# SCH_ninth-easy-stackable_2023-01-05.net
KiCad netlist of a schematic drawn in EasyEDA
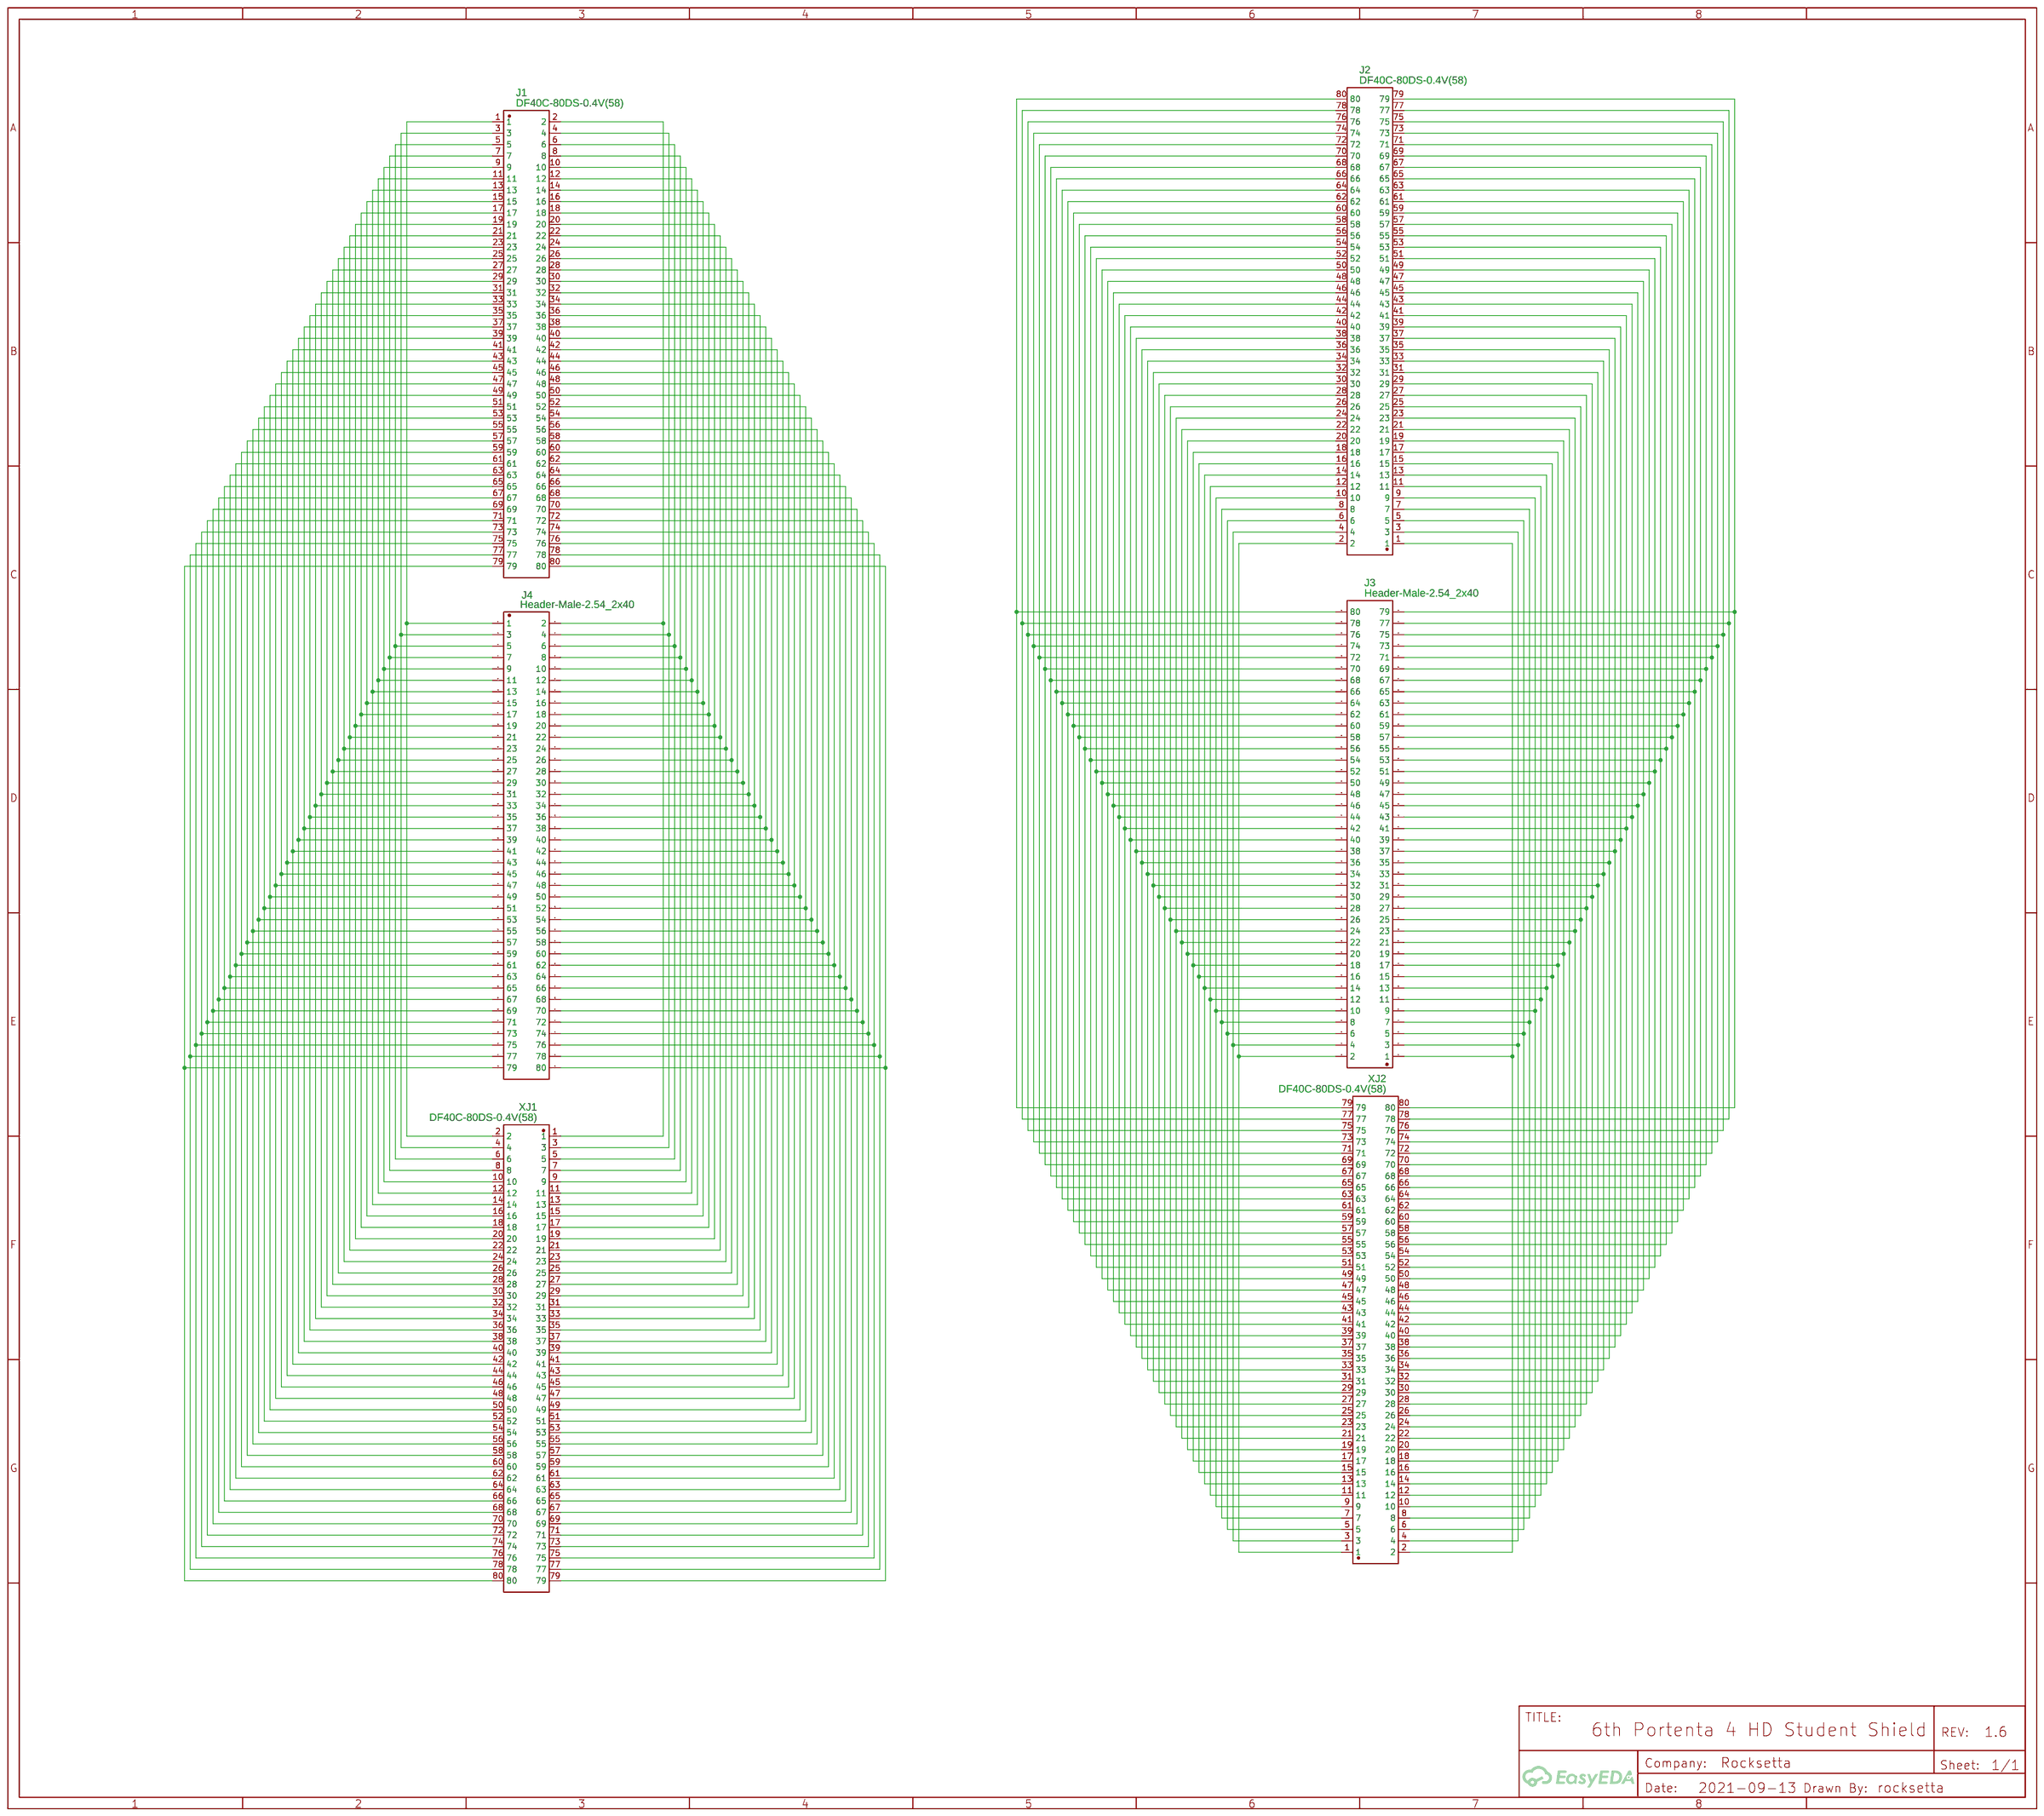
[diagram p0: schematic sheet]

(export (version "E")
  (design (tool "Eeschema 10.0.6"))
  (components
    (comp (ref "J1")
      (value "DF40C-80DS-0.4V(58)")
      (fields (field (name "BOM_Supplier Part") "C597941"))
      (libsource (lib "") (part "DF40C-80DS-0.4V(58)_2"))
    )
    (comp (ref "J2")
      (value "DF40C-80DS-0.4V(58)")
      (fields (field (name "BOM_Supplier Part") "C597941"))
      (libsource (lib "") (part "DF40C-80DS-0.4V(58)_3"))
    )
    (comp (ref "J3")
      (value "Header-Male-2.54_2x40")
      (fields
        (field (name "BOM_Manufacturer Part") "2.54mm 2x40P")
        (field (name "BOM_Supplier Part") "C2333")
      )
      (libsource (lib "") (part "Header-Male-2.54_2x40_1"))
    )
    (comp (ref "J4")
      (value "Header-Male-2.54_2x40")
      (fields
        (field (name "BOM_Manufacturer Part") "2.54mm 2x40P")
        (field (name "BOM_Supplier Part") "C2333")
      )
      (libsource (lib "") (part "Header-Male-2.54_2x40"))
    )
    (comp (ref "XJ1")
      (value "DF40C-80DS-0.4V(58)")
      (fields (field (name "BOM_Supplier Part") "C597941"))
      (libsource (lib "") (part "DF40C-80DS-0.4V(58)"))
    )
    (comp (ref "XJ2")
      (value "DF40C-80DS-0.4V(58)")
      (fields (field (name "BOM_Supplier Part") "C597941"))
      (libsource (lib "") (part "DF40C-80DS-0.4V(58)_1"))
    )
  )
  (nets
    (net (code "1") (name "Net-(J1-Pad1)") (class "Default")
      (node (ref "J1") (pin "1") (pinfunction "1_1") (pintype "unspecified"))
      (node (ref "J4") (pin "1") (pinfunction "1_1") (pintype "unspecified"))
      (node (ref "XJ1") (pin "2") (pinfunction "2_2") (pintype "unspecified"))
    )
    (net (code "2") (name "Net-(J1-Pad2)") (class "Default")
      (node (ref "J1") (pin "2") (pinfunction "2_2") (pintype "unspecified"))
      (node (ref "J4") (pin "2") (pinfunction "2_2") (pintype "unspecified"))
      (node (ref "XJ1") (pin "1") (pinfunction "1_1") (pintype "unspecified"))
    )
    (net (code "3") (name "Net-(J1-Pad3)") (class "Default")
      (node (ref "J1") (pin "3") (pinfunction "3_3") (pintype "unspecified"))
      (node (ref "J4") (pin "3") (pinfunction "3_3") (pintype "unspecified"))
      (node (ref "XJ1") (pin "4") (pinfunction "4_4") (pintype "unspecified"))
    )
    (net (code "4") (name "Net-(J1-Pad4)") (class "Default")
      (node (ref "J1") (pin "4") (pinfunction "4_4") (pintype "unspecified"))
      (node (ref "J4") (pin "4") (pinfunction "4_4") (pintype "unspecified"))
      (node (ref "XJ1") (pin "3") (pinfunction "3_3") (pintype "unspecified"))
    )
    (net (code "5") (name "Net-(J1-Pad5)") (class "Default")
      (node (ref "J1") (pin "5") (pinfunction "5_5") (pintype "unspecified"))
      (node (ref "J4") (pin "5") (pinfunction "5_5") (pintype "unspecified"))
      (node (ref "XJ1") (pin "6") (pinfunction "6_6") (pintype "unspecified"))
    )
    (net (code "6") (name "Net-(J1-Pad6)") (class "Default")
      (node (ref "J1") (pin "6") (pinfunction "6_6") (pintype "unspecified"))
      (node (ref "J4") (pin "6") (pinfunction "6_6") (pintype "unspecified"))
      (node (ref "XJ1") (pin "5") (pinfunction "5_5") (pintype "unspecified"))
    )
    (net (code "7") (name "Net-(J1-Pad7)") (class "Default")
      (node (ref "J1") (pin "7") (pinfunction "7_7") (pintype "unspecified"))
      (node (ref "J4") (pin "7") (pinfunction "7_7") (pintype "unspecified"))
      (node (ref "XJ1") (pin "8") (pinfunction "8_8") (pintype "unspecified"))
    )
    (net (code "8") (name "Net-(J1-Pad8)") (class "Default")
      (node (ref "J1") (pin "8") (pinfunction "8_8") (pintype "unspecified"))
      (node (ref "J4") (pin "8") (pinfunction "8_8") (pintype "unspecified"))
      (node (ref "XJ1") (pin "7") (pinfunction "7_7") (pintype "unspecified"))
    )
    (net (code "9") (name "Net-(J1-Pad9)") (class "Default")
      (node (ref "J1") (pin "9") (pinfunction "9_9") (pintype "unspecified"))
      (node (ref "J4") (pin "9") (pinfunction "9_9") (pintype "unspecified"))
      (node (ref "XJ1") (pin "10") (pinfunction "10_10") (pintype "unspecified"))
    )
    (net (code "10") (name "Net-(J1-Pad10)") (class "Default")
      (node (ref "J1") (pin "10") (pinfunction "10_10") (pintype "unspecified"))
      (node (ref "J4") (pin "10") (pinfunction "10_10") (pintype "unspecified"))
      (node (ref "XJ1") (pin "9") (pinfunction "9_9") (pintype "unspecified"))
    )
    (net (code "11") (name "Net-(J1-Pad11)") (class "Default")
      (node (ref "J1") (pin "11") (pinfunction "11_11") (pintype "unspecified"))
      (node (ref "J4") (pin "11") (pinfunction "11_11") (pintype "unspecified"))
      (node (ref "XJ1") (pin "12") (pinfunction "12_12") (pintype "unspecified"))
    )
    (net (code "12") (name "Net-(J1-Pad12)") (class "Default")
      (node (ref "J1") (pin "12") (pinfunction "12_12") (pintype "unspecified"))
      (node (ref "J4") (pin "12") (pinfunction "12_12") (pintype "unspecified"))
      (node (ref "XJ1") (pin "11") (pinfunction "11_11") (pintype "unspecified"))
    )
    (net (code "13") (name "Net-(J1-Pad13)") (class "Default")
      (node (ref "J1") (pin "13") (pinfunction "13_13") (pintype "unspecified"))
      (node (ref "J4") (pin "13") (pinfunction "13_13") (pintype "unspecified"))
      (node (ref "XJ1") (pin "14") (pinfunction "14_14") (pintype "unspecified"))
    )
    (net (code "14") (name "Net-(J1-Pad14)") (class "Default")
      (node (ref "J1") (pin "14") (pinfunction "14_14") (pintype "unspecified"))
      (node (ref "J4") (pin "14") (pinfunction "14_14") (pintype "unspecified"))
      (node (ref "XJ1") (pin "13") (pinfunction "13_13") (pintype "unspecified"))
    )
    (net (code "15") (name "Net-(J1-Pad15)") (class "Default")
      (node (ref "J1") (pin "15") (pinfunction "15_15") (pintype "unspecified"))
      (node (ref "J4") (pin "15") (pinfunction "15_15") (pintype "unspecified"))
      (node (ref "XJ1") (pin "16") (pinfunction "16_16") (pintype "unspecified"))
    )
    (net (code "16") (name "Net-(J1-Pad16)") (class "Default")
      (node (ref "J1") (pin "16") (pinfunction "16_16") (pintype "unspecified"))
      (node (ref "J4") (pin "16") (pinfunction "16_16") (pintype "unspecified"))
      (node (ref "XJ1") (pin "15") (pinfunction "15_15") (pintype "unspecified"))
    )
    (net (code "17") (name "Net-(J1-Pad17)") (class "Default")
      (node (ref "J1") (pin "17") (pinfunction "17_17") (pintype "unspecified"))
      (node (ref "J4") (pin "17") (pinfunction "17_17") (pintype "unspecified"))
      (node (ref "XJ1") (pin "18") (pinfunction "18_18") (pintype "unspecified"))
    )
    (net (code "18") (name "Net-(J1-Pad18)") (class "Default")
      (node (ref "J1") (pin "18") (pinfunction "18_18") (pintype "unspecified"))
      (node (ref "J4") (pin "18") (pinfunction "18_18") (pintype "unspecified"))
      (node (ref "XJ1") (pin "17") (pinfunction "17_17") (pintype "unspecified"))
    )
    (net (code "19") (name "Net-(J1-Pad19)") (class "Default")
      (node (ref "J1") (pin "19") (pinfunction "19_19") (pintype "unspecified"))
      (node (ref "J4") (pin "19") (pinfunction "19_19") (pintype "unspecified"))
      (node (ref "XJ1") (pin "20") (pinfunction "20_20") (pintype "unspecified"))
    )
    (net (code "20") (name "Net-(J1-Pad20)") (class "Default")
      (node (ref "J1") (pin "20") (pinfunction "20_20") (pintype "unspecified"))
      (node (ref "J4") (pin "20") (pinfunction "20_20") (pintype "unspecified"))
      (node (ref "XJ1") (pin "19") (pinfunction "19_19") (pintype "unspecified"))
    )
    (net (code "21") (name "Net-(J1-Pad21)") (class "Default")
      (node (ref "J1") (pin "21") (pinfunction "21_21") (pintype "unspecified"))
      (node (ref "J4") (pin "21") (pinfunction "21_21") (pintype "unspecified"))
      (node (ref "XJ1") (pin "22") (pinfunction "22_22") (pintype "unspecified"))
    )
    (net (code "22") (name "Net-(J1-Pad22)") (class "Default")
      (node (ref "J1") (pin "22") (pinfunction "22_22") (pintype "unspecified"))
      (node (ref "J4") (pin "22") (pinfunction "22_22") (pintype "unspecified"))
      (node (ref "XJ1") (pin "21") (pinfunction "21_21") (pintype "unspecified"))
    )
    (net (code "23") (name "Net-(J1-Pad23)") (class "Default")
      (node (ref "J1") (pin "23") (pinfunction "23_23") (pintype "unspecified"))
      (node (ref "J4") (pin "23") (pinfunction "23_23") (pintype "unspecified"))
      (node (ref "XJ1") (pin "24") (pinfunction "24_24") (pintype "unspecified"))
    )
    (net (code "24") (name "Net-(J1-Pad24)") (class "Default")
      (node (ref "J1") (pin "24") (pinfunction "24_24") (pintype "unspecified"))
      (node (ref "J4") (pin "24") (pinfunction "24_24") (pintype "unspecified"))
      (node (ref "XJ1") (pin "23") (pinfunction "23_23") (pintype "unspecified"))
    )
    (net (code "25") (name "Net-(J1-Pad25)") (class "Default")
      (node (ref "J1") (pin "25") (pinfunction "25_25") (pintype "unspecified"))
      (node (ref "J4") (pin "25") (pinfunction "25_25") (pintype "unspecified"))
      (node (ref "XJ1") (pin "26") (pinfunction "26_26") (pintype "unspecified"))
    )
    (net (code "26") (name "Net-(J1-Pad26)") (class "Default")
      (node (ref "J1") (pin "26") (pinfunction "26_26") (pintype "unspecified"))
      (node (ref "J4") (pin "26") (pinfunction "26_26") (pintype "unspecified"))
      (node (ref "XJ1") (pin "25") (pinfunction "25_25") (pintype "unspecified"))
    )
    (net (code "27") (name "Net-(J1-Pad27)") (class "Default")
      (node (ref "J1") (pin "27") (pinfunction "27_27") (pintype "unspecified"))
      (node (ref "J4") (pin "27") (pinfunction "27_27") (pintype "unspecified"))
      (node (ref "XJ1") (pin "28") (pinfunction "28_28") (pintype "unspecified"))
    )
    (net (code "28") (name "Net-(J1-Pad28)") (class "Default")
      (node (ref "J1") (pin "28") (pinfunction "28_28") (pintype "unspecified"))
      (node (ref "J4") (pin "28") (pinfunction "28_28") (pintype "unspecified"))
      (node (ref "XJ1") (pin "27") (pinfunction "27_27") (pintype "unspecified"))
    )
    (net (code "29") (name "Net-(J1-Pad29)") (class "Default")
      (node (ref "J1") (pin "29") (pinfunction "29_29") (pintype "unspecified"))
      (node (ref "J4") (pin "29") (pinfunction "29_29") (pintype "unspecified"))
      (node (ref "XJ1") (pin "30") (pinfunction "30_30") (pintype "unspecified"))
    )
    (net (code "30") (name "Net-(J1-Pad30)") (class "Default")
      (node (ref "J1") (pin "30") (pinfunction "30_30") (pintype "unspecified"))
      (node (ref "J4") (pin "30") (pinfunction "30_30") (pintype "unspecified"))
      (node (ref "XJ1") (pin "29") (pinfunction "29_29") (pintype "unspecified"))
    )
    (net (code "31") (name "Net-(J1-Pad31)") (class "Default")
      (node (ref "J1") (pin "31") (pinfunction "31_31") (pintype "unspecified"))
      (node (ref "J4") (pin "31") (pinfunction "31_31") (pintype "unspecified"))
      (node (ref "XJ1") (pin "32") (pinfunction "32_32") (pintype "unspecified"))
    )
    (net (code "32") (name "Net-(J1-Pad32)") (class "Default")
      (node (ref "J1") (pin "32") (pinfunction "32_32") (pintype "unspecified"))
      (node (ref "J4") (pin "32") (pinfunction "32_32") (pintype "unspecified"))
      (node (ref "XJ1") (pin "31") (pinfunction "31_31") (pintype "unspecified"))
    )
    (net (code "33") (name "Net-(J1-Pad33)") (class "Default")
      (node (ref "J1") (pin "33") (pinfunction "33_33") (pintype "unspecified"))
      (node (ref "J4") (pin "33") (pinfunction "33_33") (pintype "unspecified"))
      (node (ref "XJ1") (pin "34") (pinfunction "34_34") (pintype "unspecified"))
    )
    (net (code "34") (name "Net-(J1-Pad34)") (class "Default")
      (node (ref "J1") (pin "34") (pinfunction "34_34") (pintype "unspecified"))
      (node (ref "J4") (pin "34") (pinfunction "34_34") (pintype "unspecified"))
      (node (ref "XJ1") (pin "33") (pinfunction "33_33") (pintype "unspecified"))
    )
    (net (code "35") (name "Net-(J1-Pad35)") (class "Default")
      (node (ref "J1") (pin "35") (pinfunction "35_35") (pintype "unspecified"))
      (node (ref "J4") (pin "35") (pinfunction "35_35") (pintype "unspecified"))
      (node (ref "XJ1") (pin "36") (pinfunction "36_36") (pintype "unspecified"))
    )
    (net (code "36") (name "Net-(J1-Pad36)") (class "Default")
      (node (ref "J1") (pin "36") (pinfunction "36_36") (pintype "unspecified"))
      (node (ref "J4") (pin "36") (pinfunction "36_36") (pintype "unspecified"))
      (node (ref "XJ1") (pin "35") (pinfunction "35_35") (pintype "unspecified"))
    )
    (net (code "37") (name "Net-(J1-Pad37)") (class "Default")
      (node (ref "J1") (pin "37") (pinfunction "37_37") (pintype "unspecified"))
      (node (ref "J4") (pin "37") (pinfunction "37_37") (pintype "unspecified"))
      (node (ref "XJ1") (pin "38") (pinfunction "38_38") (pintype "unspecified"))
    )
    (net (code "38") (name "Net-(J1-Pad38)") (class "Default")
      (node (ref "J1") (pin "38") (pinfunction "38_38") (pintype "unspecified"))
      (node (ref "J4") (pin "38") (pinfunction "38_38") (pintype "unspecified"))
      (node (ref "XJ1") (pin "37") (pinfunction "37_37") (pintype "unspecified"))
    )
    (net (code "39") (name "Net-(J1-Pad39)") (class "Default")
      (node (ref "J1") (pin "39") (pinfunction "39_39") (pintype "unspecified"))
      (node (ref "J4") (pin "39") (pinfunction "39_39") (pintype "unspecified"))
      (node (ref "XJ1") (pin "40") (pinfunction "40_40") (pintype "unspecified"))
    )
    (net (code "40") (name "Net-(J1-Pad40)") (class "Default")
      (node (ref "J1") (pin "40") (pinfunction "40_40") (pintype "unspecified"))
      (node (ref "J4") (pin "40") (pinfunction "40_40") (pintype "unspecified"))
      (node (ref "XJ1") (pin "39") (pinfunction "39_39") (pintype "unspecified"))
    )
    (net (code "41") (name "Net-(J1-Pad41)") (class "Default")
      (node (ref "J1") (pin "41") (pinfunction "41_41") (pintype "unspecified"))
      (node (ref "J4") (pin "41") (pinfunction "41_41") (pintype "unspecified"))
      (node (ref "XJ1") (pin "42") (pinfunction "42_42") (pintype "unspecified"))
    )
    (net (code "42") (name "Net-(J1-Pad42)") (class "Default")
      (node (ref "J1") (pin "42") (pinfunction "42_42") (pintype "unspecified"))
      (node (ref "J4") (pin "42") (pinfunction "42_42") (pintype "unspecified"))
      (node (ref "XJ1") (pin "41") (pinfunction "41_41") (pintype "unspecified"))
    )
    (net (code "43") (name "Net-(J1-Pad43)") (class "Default")
      (node (ref "J1") (pin "43") (pinfunction "43_43") (pintype "unspecified"))
      (node (ref "J4") (pin "43") (pinfunction "43_43") (pintype "unspecified"))
      (node (ref "XJ1") (pin "44") (pinfunction "44_44") (pintype "unspecified"))
    )
    (net (code "44") (name "Net-(J1-Pad44)") (class "Default")
      (node (ref "J1") (pin "44") (pinfunction "44_44") (pintype "unspecified"))
      (node (ref "J4") (pin "44") (pinfunction "44_44") (pintype "unspecified"))
      (node (ref "XJ1") (pin "43") (pinfunction "43_43") (pintype "unspecified"))
    )
    (net (code "45") (name "Net-(J1-Pad45)") (class "Default")
      (node (ref "J1") (pin "45") (pinfunction "45_45") (pintype "unspecified"))
      (node (ref "J4") (pin "45") (pinfunction "45_45") (pintype "unspecified"))
      (node (ref "XJ1") (pin "46") (pinfunction "46_46") (pintype "unspecified"))
    )
    (net (code "46") (name "Net-(J1-Pad46)") (class "Default")
      (node (ref "J1") (pin "46") (pinfunction "46_46") (pintype "unspecified"))
      (node (ref "J4") (pin "46") (pinfunction "46_46") (pintype "unspecified"))
      (node (ref "XJ1") (pin "45") (pinfunction "45_45") (pintype "unspecified"))
    )
    (net (code "47") (name "Net-(J1-Pad47)") (class "Default")
      (node (ref "J1") (pin "47") (pinfunction "47_47") (pintype "unspecified"))
      (node (ref "J4") (pin "47") (pinfunction "47_47") (pintype "unspecified"))
      (node (ref "XJ1") (pin "48") (pinfunction "48_48") (pintype "unspecified"))
    )
    (net (code "48") (name "Net-(J1-Pad48)") (class "Default")
      (node (ref "J1") (pin "48") (pinfunction "48_48") (pintype "unspecified"))
      (node (ref "J4") (pin "48") (pinfunction "48_48") (pintype "unspecified"))
      (node (ref "XJ1") (pin "47") (pinfunction "47_47") (pintype "unspecified"))
    )
    (net (code "49") (name "Net-(J1-Pad49)") (class "Default")
      (node (ref "J1") (pin "49") (pinfunction "49_49") (pintype "unspecified"))
      (node (ref "J4") (pin "49") (pinfunction "49_49") (pintype "unspecified"))
      (node (ref "XJ1") (pin "50") (pinfunction "50_50") (pintype "unspecified"))
    )
    (net (code "50") (name "Net-(J1-Pad50)") (class "Default")
      (node (ref "J1") (pin "50") (pinfunction "50_50") (pintype "unspecified"))
      (node (ref "J4") (pin "50") (pinfunction "50_50") (pintype "unspecified"))
      (node (ref "XJ1") (pin "49") (pinfunction "49_49") (pintype "unspecified"))
    )
    (net (code "51") (name "Net-(J1-Pad51)") (class "Default")
      (node (ref "J1") (pin "51") (pinfunction "51_51") (pintype "unspecified"))
      (node (ref "J4") (pin "51") (pinfunction "51_51") (pintype "unspecified"))
      (node (ref "XJ1") (pin "52") (pinfunction "52_52") (pintype "unspecified"))
    )
    (net (code "52") (name "Net-(J1-Pad52)") (class "Default")
      (node (ref "J1") (pin "52") (pinfunction "52_52") (pintype "unspecified"))
      (node (ref "J4") (pin "52") (pinfunction "52_52") (pintype "unspecified"))
      (node (ref "XJ1") (pin "51") (pinfunction "51_51") (pintype "unspecified"))
    )
    (net (code "53") (name "Net-(J1-Pad53)") (class "Default")
      (node (ref "J1") (pin "53") (pinfunction "53_53") (pintype "unspecified"))
      (node (ref "J4") (pin "53") (pinfunction "53_53") (pintype "unspecified"))
      (node (ref "XJ1") (pin "54") (pinfunction "54_54") (pintype "unspecified"))
    )
    (net (code "54") (name "Net-(J1-Pad54)") (class "Default")
      (node (ref "J1") (pin "54") (pinfunction "54_54") (pintype "unspecified"))
      (node (ref "J4") (pin "54") (pinfunction "54_54") (pintype "unspecified"))
      (node (ref "XJ1") (pin "53") (pinfunction "53_53") (pintype "unspecified"))
    )
    (net (code "55") (name "Net-(J1-Pad55)") (class "Default")
      (node (ref "J1") (pin "55") (pinfunction "55_55") (pintype "unspecified"))
      (node (ref "J4") (pin "55") (pinfunction "55_55") (pintype "unspecified"))
      (node (ref "XJ1") (pin "56") (pinfunction "56_56") (pintype "unspecified"))
    )
    (net (code "56") (name "Net-(J1-Pad56)") (class "Default")
      (node (ref "J1") (pin "56") (pinfunction "56_56") (pintype "unspecified"))
      (node (ref "J4") (pin "56") (pinfunction "56_56") (pintype "unspecified"))
      (node (ref "XJ1") (pin "55") (pinfunction "55_55") (pintype "unspecified"))
    )
    (net (code "57") (name "Net-(J1-Pad57)") (class "Default")
      (node (ref "J1") (pin "57") (pinfunction "57_57") (pintype "unspecified"))
      (node (ref "J4") (pin "57") (pinfunction "57_57") (pintype "unspecified"))
      (node (ref "XJ1") (pin "58") (pinfunction "58_58") (pintype "unspecified"))
    )
    (net (code "58") (name "Net-(J1-Pad58)") (class "Default")
      (node (ref "J1") (pin "58") (pinfunction "58_58") (pintype "unspecified"))
      (node (ref "J4") (pin "58") (pinfunction "58_58") (pintype "unspecified"))
      (node (ref "XJ1") (pin "57") (pinfunction "57_57") (pintype "unspecified"))
    )
    (net (code "59") (name "Net-(J1-Pad59)") (class "Default")
      (node (ref "J1") (pin "59") (pinfunction "59_59") (pintype "unspecified"))
      (node (ref "J4") (pin "59") (pinfunction "59_59") (pintype "unspecified"))
      (node (ref "XJ1") (pin "60") (pinfunction "60_60") (pintype "unspecified"))
    )
    (net (code "60") (name "Net-(J1-Pad60)") (class "Default")
      (node (ref "J1") (pin "60") (pinfunction "60_60") (pintype "unspecified"))
      (node (ref "J4") (pin "60") (pinfunction "60_60") (pintype "unspecified"))
      (node (ref "XJ1") (pin "59") (pinfunction "59_59") (pintype "unspecified"))
    )
    (net (code "61") (name "Net-(J1-Pad61)") (class "Default")
      (node (ref "J1") (pin "61") (pinfunction "61_61") (pintype "unspecified"))
      (node (ref "J4") (pin "61") (pinfunction "61_61") (pintype "unspecified"))
      (node (ref "XJ1") (pin "62") (pinfunction "62_62") (pintype "unspecified"))
    )
    (net (code "62") (name "Net-(J1-Pad62)") (class "Default")
      (node (ref "J1") (pin "62") (pinfunction "62_62") (pintype "unspecified"))
      (node (ref "J4") (pin "62") (pinfunction "62_62") (pintype "unspecified"))
      (node (ref "XJ1") (pin "61") (pinfunction "61_61") (pintype "unspecified"))
    )
    (net (code "63") (name "Net-(J1-Pad63)") (class "Default")
      (node (ref "J1") (pin "63") (pinfunction "63_63") (pintype "unspecified"))
      (node (ref "J4") (pin "63") (pinfunction "63_63") (pintype "unspecified"))
      (node (ref "XJ1") (pin "64") (pinfunction "64_64") (pintype "unspecified"))
    )
    (net (code "64") (name "Net-(J1-Pad64)") (class "Default")
      (node (ref "J1") (pin "64") (pinfunction "64_64") (pintype "unspecified"))
      (node (ref "J4") (pin "64") (pinfunction "64_64") (pintype "unspecified"))
      (node (ref "XJ1") (pin "63") (pinfunction "63_63") (pintype "unspecified"))
    )
    (net (code "65") (name "Net-(J1-Pad65)") (class "Default")
      (node (ref "J1") (pin "65") (pinfunction "65_65") (pintype "unspecified"))
      (node (ref "J4") (pin "65") (pinfunction "65_65") (pintype "unspecified"))
      (node (ref "XJ1") (pin "66") (pinfunction "66_66") (pintype "unspecified"))
    )
    (net (code "66") (name "Net-(J1-Pad66)") (class "Default")
      (node (ref "J1") (pin "66") (pinfunction "66_66") (pintype "unspecified"))
      (node (ref "J4") (pin "66") (pinfunction "66_66") (pintype "unspecified"))
      (node (ref "XJ1") (pin "65") (pinfunction "65_65") (pintype "unspecified"))
    )
    (net (code "67") (name "Net-(J1-Pad67)") (class "Default")
      (node (ref "J1") (pin "67") (pinfunction "67_67") (pintype "unspecified"))
      (node (ref "J4") (pin "67") (pinfunction "67_67") (pintype "unspecified"))
      (node (ref "XJ1") (pin "68") (pinfunction "68_68") (pintype "unspecified"))
    )
    (net (code "68") (name "Net-(J1-Pad68)") (class "Default")
      (node (ref "J1") (pin "68") (pinfunction "68_68") (pintype "unspecified"))
      (node (ref "J4") (pin "68") (pinfunction "68_68") (pintype "unspecified"))
      (node (ref "XJ1") (pin "67") (pinfunction "67_67") (pintype "unspecified"))
    )
    (net (code "69") (name "Net-(J1-Pad69)") (class "Default")
      (node (ref "J1") (pin "69") (pinfunction "69_69") (pintype "unspecified"))
      (node (ref "J4") (pin "69") (pinfunction "69_69") (pintype "unspecified"))
      (node (ref "XJ1") (pin "70") (pinfunction "70_70") (pintype "unspecified"))
    )
    (net (code "70") (name "Net-(J1-Pad70)") (class "Default")
      (node (ref "J1") (pin "70") (pinfunction "70_70") (pintype "unspecified"))
      (node (ref "J4") (pin "70") (pinfunction "70_70") (pintype "unspecified"))
      (node (ref "XJ1") (pin "69") (pinfunction "69_69") (pintype "unspecified"))
    )
    (net (code "71") (name "Net-(J1-Pad71)") (class "Default")
      (node (ref "J1") (pin "71") (pinfunction "71_71") (pintype "unspecified"))
      (node (ref "J4") (pin "71") (pinfunction "71_71") (pintype "unspecified"))
      (node (ref "XJ1") (pin "72") (pinfunction "72_72") (pintype "unspecified"))
    )
    (net (code "72") (name "Net-(J1-Pad72)") (class "Default")
      (node (ref "J1") (pin "72") (pinfunction "72_72") (pintype "unspecified"))
      (node (ref "J4") (pin "72") (pinfunction "72_72") (pintype "unspecified"))
      (node (ref "XJ1") (pin "71") (pinfunction "71_71") (pintype "unspecified"))
    )
    (net (code "73") (name "Net-(J1-Pad73)") (class "Default")
      (node (ref "J1") (pin "73") (pinfunction "73_73") (pintype "unspecified"))
      (node (ref "J4") (pin "73") (pinfunction "73_73") (pintype "unspecified"))
      (node (ref "XJ1") (pin "74") (pinfunction "74_74") (pintype "unspecified"))
    )
    (net (code "74") (name "Net-(J1-Pad74)") (class "Default")
      (node (ref "J1") (pin "74") (pinfunction "74_74") (pintype "unspecified"))
      (node (ref "J4") (pin "74") (pinfunction "74_74") (pintype "unspecified"))
      (node (ref "XJ1") (pin "73") (pinfunction "73_73") (pintype "unspecified"))
    )
    (net (code "75") (name "Net-(J1-Pad75)") (class "Default")
      (node (ref "J1") (pin "75") (pinfunction "75_75") (pintype "unspecified"))
      (node (ref "J4") (pin "75") (pinfunction "75_75") (pintype "unspecified"))
      (node (ref "XJ1") (pin "76") (pinfunction "76_76") (pintype "unspecified"))
    )
    (net (code "76") (name "Net-(J1-Pad76)") (class "Default")
      (node (ref "J1") (pin "76") (pinfunction "76_76") (pintype "unspecified"))
      (node (ref "J4") (pin "76") (pinfunction "76_76") (pintype "unspecified"))
      (node (ref "XJ1") (pin "75") (pinfunction "75_75") (pintype "unspecified"))
    )
    (net (code "77") (name "Net-(J1-Pad77)") (class "Default")
      (node (ref "J1") (pin "77") (pinfunction "77_77") (pintype "unspecified"))
      (node (ref "J4") (pin "77") (pinfunction "77_77") (pintype "unspecified"))
      (node (ref "XJ1") (pin "78") (pinfunction "78_78") (pintype "unspecified"))
    )
    (net (code "78") (name "Net-(J1-Pad78)") (class "Default")
      (node (ref "J1") (pin "78") (pinfunction "78_78") (pintype "unspecified"))
      (node (ref "J4") (pin "78") (pinfunction "78_78") (pintype "unspecified"))
      (node (ref "XJ1") (pin "77") (pinfunction "77_77") (pintype "unspecified"))
    )
    (net (code "79") (name "Net-(J1-Pad79)") (class "Default")
      (node (ref "J1") (pin "79") (pinfunction "79_79") (pintype "unspecified"))
      (node (ref "J4") (pin "79") (pinfunction "79_79") (pintype "unspecified"))
      (node (ref "XJ1") (pin "80") (pinfunction "80_80") (pintype "unspecified"))
    )
    (net (code "80") (name "Net-(J1-Pad80)") (class "Default")
      (node (ref "J1") (pin "80") (pinfunction "80_80") (pintype "unspecified"))
      (node (ref "J4") (pin "80") (pinfunction "80_80") (pintype "unspecified"))
      (node (ref "XJ1") (pin "79") (pinfunction "79_79") (pintype "unspecified"))
    )
    (net (code "81") (name "Net-(J2-Pad1)") (class "Default")
      (node (ref "J2") (pin "1") (pinfunction "1_1") (pintype "unspecified"))
      (node (ref "J3") (pin "1") (pinfunction "1_1") (pintype "unspecified"))
      (node (ref "XJ2") (pin "2") (pinfunction "2_2") (pintype "unspecified"))
    )
    (net (code "82") (name "Net-(J2-Pad2)") (class "Default")
      (node (ref "J2") (pin "2") (pinfunction "2_2") (pintype "unspecified"))
      (node (ref "J3") (pin "2") (pinfunction "2_2") (pintype "unspecified"))
      (node (ref "XJ2") (pin "1") (pinfunction "1_1") (pintype "unspecified"))
    )
    (net (code "83") (name "Net-(J2-Pad3)") (class "Default")
      (node (ref "J2") (pin "3") (pinfunction "3_3") (pintype "unspecified"))
      (node (ref "J3") (pin "3") (pinfunction "3_3") (pintype "unspecified"))
      (node (ref "XJ2") (pin "4") (pinfunction "4_4") (pintype "unspecified"))
    )
    (net (code "84") (name "Net-(J2-Pad4)") (class "Default")
      (node (ref "J2") (pin "4") (pinfunction "4_4") (pintype "unspecified"))
      (node (ref "J3") (pin "4") (pinfunction "4_4") (pintype "unspecified"))
      (node (ref "XJ2") (pin "3") (pinfunction "3_3") (pintype "unspecified"))
    )
    (net (code "85") (name "Net-(J2-Pad5)") (class "Default")
      (node (ref "J2") (pin "5") (pinfunction "5_5") (pintype "unspecified"))
      (node (ref "J3") (pin "5") (pinfunction "5_5") (pintype "unspecified"))
      (node (ref "XJ2") (pin "6") (pinfunction "6_6") (pintype "unspecified"))
    )
    (net (code "86") (name "Net-(J2-Pad6)") (class "Default")
      (node (ref "J2") (pin "6") (pinfunction "6_6") (pintype "unspecified"))
      (node (ref "J3") (pin "6") (pinfunction "6_6") (pintype "unspecified"))
      (node (ref "XJ2") (pin "5") (pinfunction "5_5") (pintype "unspecified"))
    )
    (net (code "87") (name "Net-(J2-Pad7)") (class "Default")
      (node (ref "J2") (pin "7") (pinfunction "7_7") (pintype "unspecified"))
      (node (ref "J3") (pin "7") (pinfunction "7_7") (pintype "unspecified"))
      (node (ref "XJ2") (pin "8") (pinfunction "8_8") (pintype "unspecified"))
    )
    (net (code "88") (name "Net-(J2-Pad8)") (class "Default")
      (node (ref "J2") (pin "8") (pinfunction "8_8") (pintype "unspecified"))
      (node (ref "J3") (pin "8") (pinfunction "8_8") (pintype "unspecified"))
      (node (ref "XJ2") (pin "7") (pinfunction "7_7") (pintype "unspecified"))
    )
    (net (code "89") (name "Net-(J2-Pad9)") (class "Default")
      (node (ref "J2") (pin "9") (pinfunction "9_9") (pintype "unspecified"))
      (node (ref "J3") (pin "9") (pinfunction "9_9") (pintype "unspecified"))
      (node (ref "XJ2") (pin "10") (pinfunction "10_10") (pintype "unspecified"))
    )
    (net (code "90") (name "Net-(J2-Pad10)") (class "Default")
      (node (ref "J2") (pin "10") (pinfunction "10_10") (pintype "unspecified"))
      (node (ref "J3") (pin "10") (pinfunction "10_10") (pintype "unspecified"))
      (node (ref "XJ2") (pin "9") (pinfunction "9_9") (pintype "unspecified"))
    )
    (net (code "91") (name "Net-(J2-Pad11)") (class "Default")
      (node (ref "J2") (pin "11") (pinfunction "11_11") (pintype "unspecified"))
      (node (ref "J3") (pin "11") (pinfunction "11_11") (pintype "unspecified"))
      (node (ref "XJ2") (pin "12") (pinfunction "12_12") (pintype "unspecified"))
    )
    (net (code "92") (name "Net-(J2-Pad12)") (class "Default")
      (node (ref "J2") (pin "12") (pinfunction "12_12") (pintype "unspecified"))
      (node (ref "J3") (pin "12") (pinfunction "12_12") (pintype "unspecified"))
      (node (ref "XJ2") (pin "11") (pinfunction "11_11") (pintype "unspecified"))
    )
    (net (code "93") (name "Net-(J2-Pad13)") (class "Default")
      (node (ref "J2") (pin "13") (pinfunction "13_13") (pintype "unspecified"))
      (node (ref "J3") (pin "13") (pinfunction "13_13") (pintype "unspecified"))
      (node (ref "XJ2") (pin "14") (pinfunction "14_14") (pintype "unspecified"))
    )
    (net (code "94") (name "Net-(J2-Pad14)") (class "Default")
      (node (ref "J2") (pin "14") (pinfunction "14_14") (pintype "unspecified"))
      (node (ref "J3") (pin "14") (pinfunction "14_14") (pintype "unspecified"))
      (node (ref "XJ2") (pin "13") (pinfunction "13_13") (pintype "unspecified"))
    )
    (net (code "95") (name "Net-(J2-Pad15)") (class "Default")
      (node (ref "J2") (pin "15") (pinfunction "15_15") (pintype "unspecified"))
      (node (ref "J3") (pin "15") (pinfunction "15_15") (pintype "unspecified"))
      (node (ref "XJ2") (pin "16") (pinfunction "16_16") (pintype "unspecified"))
    )
    (net (code "96") (name "Net-(J2-Pad16)") (class "Default")
      (node (ref "J2") (pin "16") (pinfunction "16_16") (pintype "unspecified"))
      (node (ref "J3") (pin "16") (pinfunction "16_16") (pintype "unspecified"))
      (node (ref "XJ2") (pin "15") (pinfunction "15_15") (pintype "unspecified"))
    )
    (net (code "97") (name "Net-(J2-Pad17)") (class "Default")
      (node (ref "J2") (pin "17") (pinfunction "17_17") (pintype "unspecified"))
      (node (ref "J3") (pin "17") (pinfunction "17_17") (pintype "unspecified"))
      (node (ref "XJ2") (pin "18") (pinfunction "18_18") (pintype "unspecified"))
    )
    (net (code "98") (name "Net-(J2-Pad18)") (class "Default")
      (node (ref "J2") (pin "18") (pinfunction "18_18") (pintype "unspecified"))
      (node (ref "J3") (pin "18") (pinfunction "18_18") (pintype "unspecified"))
      (node (ref "XJ2") (pin "17") (pinfunction "17_17") (pintype "unspecified"))
    )
    (net (code "99") (name "Net-(J2-Pad19)") (class "Default")
      (node (ref "J2") (pin "19") (pinfunction "19_19") (pintype "unspecified"))
      (node (ref "J3") (pin "19") (pinfunction "19_19") (pintype "unspecified"))
      (node (ref "XJ2") (pin "20") (pinfunction "20_20") (pintype "unspecified"))
    )
    (net (code "100") (name "Net-(J2-Pad20)") (class "Default")
      (node (ref "J2") (pin "20") (pinfunction "20_20") (pintype "unspecified"))
      (node (ref "J3") (pin "20") (pinfunction "20_20") (pintype "unspecified"))
      (node (ref "XJ2") (pin "19") (pinfunction "19_19") (pintype "unspecified"))
    )
    (net (code "101") (name "Net-(J2-Pad21)") (class "Default")
      (node (ref "J2") (pin "21") (pinfunction "21_21") (pintype "unspecified"))
      (node (ref "J3") (pin "21") (pinfunction "21_21") (pintype "unspecified"))
      (node (ref "XJ2") (pin "22") (pinfunction "22_22") (pintype "unspecified"))
    )
    (net (code "102") (name "Net-(J2-Pad22)") (class "Default")
      (node (ref "J2") (pin "22") (pinfunction "22_22") (pintype "unspecified"))
      (node (ref "J3") (pin "22") (pinfunction "22_22") (pintype "unspecified"))
      (node (ref "XJ2") (pin "21") (pinfunction "21_21") (pintype "unspecified"))
    )
    (net (code "103") (name "Net-(J2-Pad23)") (class "Default")
      (node (ref "J2") (pin "23") (pinfunction "23_23") (pintype "unspecified"))
      (node (ref "J3") (pin "23") (pinfunction "23_23") (pintype "unspecified"))
      (node (ref "XJ2") (pin "24") (pinfunction "24_24") (pintype "unspecified"))
    )
    (net (code "104") (name "Net-(J2-Pad24)") (class "Default")
      (node (ref "J2") (pin "24") (pinfunction "24_24") (pintype "unspecified"))
      (node (ref "J3") (pin "24") (pinfunction "24_24") (pintype "unspecified"))
      (node (ref "XJ2") (pin "23") (pinfunction "23_23") (pintype "unspecified"))
    )
    (net (code "105") (name "Net-(J2-Pad25)") (class "Default")
      (node (ref "J2") (pin "25") (pinfunction "25_25") (pintype "unspecified"))
      (node (ref "J3") (pin "25") (pinfunction "25_25") (pintype "unspecified"))
      (node (ref "XJ2") (pin "26") (pinfunction "26_26") (pintype "unspecified"))
    )
    (net (code "106") (name "Net-(J2-Pad26)") (class "Default")
      (node (ref "J2") (pin "26") (pinfunction "26_26") (pintype "unspecified"))
      (node (ref "J3") (pin "26") (pinfunction "26_26") (pintype "unspecified"))
      (node (ref "XJ2") (pin "25") (pinfunction "25_25") (pintype "unspecified"))
    )
    (net (code "107") (name "Net-(J2-Pad27)") (class "Default")
      (node (ref "J2") (pin "27") (pinfunction "27_27") (pintype "unspecified"))
      (node (ref "J3") (pin "27") (pinfunction "27_27") (pintype "unspecified"))
      (node (ref "XJ2") (pin "28") (pinfunction "28_28") (pintype "unspecified"))
    )
    (net (code "108") (name "Net-(J2-Pad28)") (class "Default")
      (node (ref "J2") (pin "28") (pinfunction "28_28") (pintype "unspecified"))
      (node (ref "J3") (pin "28") (pinfunction "28_28") (pintype "unspecified"))
      (node (ref "XJ2") (pin "27") (pinfunction "27_27") (pintype "unspecified"))
    )
    (net (code "109") (name "Net-(J2-Pad29)") (class "Default")
      (node (ref "J2") (pin "29") (pinfunction "29_29") (pintype "unspecified"))
      (node (ref "J3") (pin "29") (pinfunction "29_29") (pintype "unspecified"))
      (node (ref "XJ2") (pin "30") (pinfunction "30_30") (pintype "unspecified"))
    )
    (net (code "110") (name "Net-(J2-Pad30)") (class "Default")
      (node (ref "J2") (pin "30") (pinfunction "30_30") (pintype "unspecified"))
      (node (ref "J3") (pin "30") (pinfunction "30_30") (pintype "unspecified"))
      (node (ref "XJ2") (pin "29") (pinfunction "29_29") (pintype "unspecified"))
    )
    (net (code "111") (name "Net-(J2-Pad31)") (class "Default")
      (node (ref "J2") (pin "31") (pinfunction "31_31") (pintype "unspecified"))
      (node (ref "J3") (pin "31") (pinfunction "31_31") (pintype "unspecified"))
      (node (ref "XJ2") (pin "32") (pinfunction "32_32") (pintype "unspecified"))
    )
    (net (code "112") (name "Net-(J2-Pad32)") (class "Default")
      (node (ref "J2") (pin "32") (pinfunction "32_32") (pintype "unspecified"))
      (node (ref "J3") (pin "32") (pinfunction "32_32") (pintype "unspecified"))
      (node (ref "XJ2") (pin "31") (pinfunction "31_31") (pintype "unspecified"))
    )
    (net (code "113") (name "Net-(J2-Pad33)") (class "Default")
      (node (ref "J2") (pin "33") (pinfunction "33_33") (pintype "unspecified"))
      (node (ref "J3") (pin "33") (pinfunction "33_33") (pintype "unspecified"))
      (node (ref "XJ2") (pin "34") (pinfunction "34_34") (pintype "unspecified"))
    )
    (net (code "114") (name "Net-(J2-Pad34)") (class "Default")
      (node (ref "J2") (pin "34") (pinfunction "34_34") (pintype "unspecified"))
      (node (ref "J3") (pin "34") (pinfunction "34_34") (pintype "unspecified"))
      (node (ref "XJ2") (pin "33") (pinfunction "33_33") (pintype "unspecified"))
    )
    (net (code "115") (name "Net-(J2-Pad35)") (class "Default")
      (node (ref "J2") (pin "35") (pinfunction "35_35") (pintype "unspecified"))
      (node (ref "J3") (pin "35") (pinfunction "35_35") (pintype "unspecified"))
      (node (ref "XJ2") (pin "36") (pinfunction "36_36") (pintype "unspecified"))
    )
    (net (code "116") (name "Net-(J2-Pad36)") (class "Default")
      (node (ref "J2") (pin "36") (pinfunction "36_36") (pintype "unspecified"))
      (node (ref "J3") (pin "36") (pinfunction "36_36") (pintype "unspecified"))
      (node (ref "XJ2") (pin "35") (pinfunction "35_35") (pintype "unspecified"))
    )
    (net (code "117") (name "Net-(J2-Pad37)") (class "Default")
      (node (ref "J2") (pin "37") (pinfunction "37_37") (pintype "unspecified"))
      (node (ref "J3") (pin "37") (pinfunction "37_37") (pintype "unspecified"))
      (node (ref "XJ2") (pin "38") (pinfunction "38_38") (pintype "unspecified"))
    )
    (net (code "118") (name "Net-(J2-Pad38)") (class "Default")
      (node (ref "J2") (pin "38") (pinfunction "38_38") (pintype "unspecified"))
      (node (ref "J3") (pin "38") (pinfunction "38_38") (pintype "unspecified"))
      (node (ref "XJ2") (pin "37") (pinfunction "37_37") (pintype "unspecified"))
    )
    (net (code "119") (name "Net-(J2-Pad39)") (class "Default")
      (node (ref "J2") (pin "39") (pinfunction "39_39") (pintype "unspecified"))
      (node (ref "J3") (pin "39") (pinfunction "39_39") (pintype "unspecified"))
      (node (ref "XJ2") (pin "40") (pinfunction "40_40") (pintype "unspecified"))
    )
    (net (code "120") (name "Net-(J2-Pad40)") (class "Default")
      (node (ref "J2") (pin "40") (pinfunction "40_40") (pintype "unspecified"))
      (node (ref "J3") (pin "40") (pinfunction "40_40") (pintype "unspecified"))
      (node (ref "XJ2") (pin "39") (pinfunction "39_39") (pintype "unspecified"))
    )
    (net (code "121") (name "Net-(J2-Pad41)") (class "Default")
      (node (ref "J2") (pin "41") (pinfunction "41_41") (pintype "unspecified"))
      (node (ref "J3") (pin "41") (pinfunction "41_41") (pintype "unspecified"))
      (node (ref "XJ2") (pin "42") (pinfunction "42_42") (pintype "unspecified"))
    )
    (net (code "122") (name "Net-(J2-Pad42)") (class "Default")
      (node (ref "J2") (pin "42") (pinfunction "42_42") (pintype "unspecified"))
      (node (ref "J3") (pin "42") (pinfunction "42_42") (pintype "unspecified"))
      (node (ref "XJ2") (pin "41") (pinfunction "41_41") (pintype "unspecified"))
    )
    (net (code "123") (name "Net-(J2-Pad43)") (class "Default")
      (node (ref "J2") (pin "43") (pinfunction "43_43") (pintype "unspecified"))
      (node (ref "J3") (pin "43") (pinfunction "43_43") (pintype "unspecified"))
      (node (ref "XJ2") (pin "44") (pinfunction "44_44") (pintype "unspecified"))
    )
    (net (code "124") (name "Net-(J2-Pad44)") (class "Default")
      (node (ref "J2") (pin "44") (pinfunction "44_44") (pintype "unspecified"))
      (node (ref "J3") (pin "44") (pinfunction "44_44") (pintype "unspecified"))
      (node (ref "XJ2") (pin "43") (pinfunction "43_43") (pintype "unspecified"))
    )
    (net (code "125") (name "Net-(J2-Pad45)") (class "Default")
      (node (ref "J2") (pin "45") (pinfunction "45_45") (pintype "unspecified"))
      (node (ref "J3") (pin "45") (pinfunction "45_45") (pintype "unspecified"))
      (node (ref "XJ2") (pin "46") (pinfunction "46_46") (pintype "unspecified"))
    )
    (net (code "126") (name "Net-(J2-Pad46)") (class "Default")
      (node (ref "J2") (pin "46") (pinfunction "46_46") (pintype "unspecified"))
      (node (ref "J3") (pin "46") (pinfunction "46_46") (pintype "unspecified"))
      (node (ref "XJ2") (pin "45") (pinfunction "45_45") (pintype "unspecified"))
    )
    (net (code "127") (name "Net-(J2-Pad47)") (class "Default")
      (node (ref "J2") (pin "47") (pinfunction "47_47") (pintype "unspecified"))
      (node (ref "J3") (pin "47") (pinfunction "47_47") (pintype "unspecified"))
      (node (ref "XJ2") (pin "48") (pinfunction "48_48") (pintype "unspecified"))
    )
    (net (code "128") (name "Net-(J2-Pad48)") (class "Default")
      (node (ref "J2") (pin "48") (pinfunction "48_48") (pintype "unspecified"))
      (node (ref "J3") (pin "48") (pinfunction "48_48") (pintype "unspecified"))
      (node (ref "XJ2") (pin "47") (pinfunction "47_47") (pintype "unspecified"))
    )
    (net (code "129") (name "Net-(J2-Pad49)") (class "Default")
      (node (ref "J2") (pin "49") (pinfunction "49_49") (pintype "unspecified"))
      (node (ref "J3") (pin "49") (pinfunction "49_49") (pintype "unspecified"))
      (node (ref "XJ2") (pin "50") (pinfunction "50_50") (pintype "unspecified"))
    )
    (net (code "130") (name "Net-(J2-Pad50)") (class "Default")
      (node (ref "J2") (pin "50") (pinfunction "50_50") (pintype "unspecified"))
      (node (ref "J3") (pin "50") (pinfunction "50_50") (pintype "unspecified"))
      (node (ref "XJ2") (pin "49") (pinfunction "49_49") (pintype "unspecified"))
    )
    (net (code "131") (name "Net-(J2-Pad51)") (class "Default")
      (node (ref "J2") (pin "51") (pinfunction "51_51") (pintype "unspecified"))
      (node (ref "J3") (pin "51") (pinfunction "51_51") (pintype "unspecified"))
      (node (ref "XJ2") (pin "52") (pinfunction "52_52") (pintype "unspecified"))
    )
    (net (code "132") (name "Net-(J2-Pad52)") (class "Default")
      (node (ref "J2") (pin "52") (pinfunction "52_52") (pintype "unspecified"))
      (node (ref "J3") (pin "52") (pinfunction "52_52") (pintype "unspecified"))
      (node (ref "XJ2") (pin "51") (pinfunction "51_51") (pintype "unspecified"))
    )
    (net (code "133") (name "Net-(J2-Pad53)") (class "Default")
      (node (ref "J2") (pin "53") (pinfunction "53_53") (pintype "unspecified"))
      (node (ref "J3") (pin "53") (pinfunction "53_53") (pintype "unspecified"))
      (node (ref "XJ2") (pin "54") (pinfunction "54_54") (pintype "unspecified"))
    )
    (net (code "134") (name "Net-(J2-Pad54)") (class "Default")
      (node (ref "J2") (pin "54") (pinfunction "54_54") (pintype "unspecified"))
      (node (ref "J3") (pin "54") (pinfunction "54_54") (pintype "unspecified"))
      (node (ref "XJ2") (pin "53") (pinfunction "53_53") (pintype "unspecified"))
    )
    (net (code "135") (name "Net-(J2-Pad55)") (class "Default")
      (node (ref "J2") (pin "55") (pinfunction "55_55") (pintype "unspecified"))
      (node (ref "J3") (pin "55") (pinfunction "55_55") (pintype "unspecified"))
      (node (ref "XJ2") (pin "56") (pinfunction "56_56") (pintype "unspecified"))
    )
    (net (code "136") (name "Net-(J2-Pad56)") (class "Default")
      (node (ref "J2") (pin "56") (pinfunction "56_56") (pintype "unspecified"))
      (node (ref "J3") (pin "56") (pinfunction "56_56") (pintype "unspecified"))
      (node (ref "XJ2") (pin "55") (pinfunction "55_55") (pintype "unspecified"))
    )
    (net (code "137") (name "Net-(J2-Pad57)") (class "Default")
      (node (ref "J2") (pin "57") (pinfunction "57_57") (pintype "unspecified"))
      (node (ref "J3") (pin "57") (pinfunction "57_57") (pintype "unspecified"))
      (node (ref "XJ2") (pin "58") (pinfunction "58_58") (pintype "unspecified"))
    )
    (net (code "138") (name "Net-(J2-Pad58)") (class "Default")
      (node (ref "J2") (pin "58") (pinfunction "58_58") (pintype "unspecified"))
      (node (ref "J3") (pin "58") (pinfunction "58_58") (pintype "unspecified"))
      (node (ref "XJ2") (pin "57") (pinfunction "57_57") (pintype "unspecified"))
    )
    (net (code "139") (name "Net-(J2-Pad59)") (class "Default")
      (node (ref "J2") (pin "59") (pinfunction "59_59") (pintype "unspecified"))
      (node (ref "J3") (pin "59") (pinfunction "59_59") (pintype "unspecified"))
      (node (ref "XJ2") (pin "60") (pinfunction "60_60") (pintype "unspecified"))
    )
    (net (code "140") (name "Net-(J2-Pad60)") (class "Default")
      (node (ref "J2") (pin "60") (pinfunction "60_60") (pintype "unspecified"))
      (node (ref "J3") (pin "60") (pinfunction "60_60") (pintype "unspecified"))
      (node (ref "XJ2") (pin "59") (pinfunction "59_59") (pintype "unspecified"))
    )
    (net (code "141") (name "Net-(J2-Pad61)") (class "Default")
      (node (ref "J2") (pin "61") (pinfunction "61_61") (pintype "unspecified"))
      (node (ref "J3") (pin "61") (pinfunction "61_61") (pintype "unspecified"))
      (node (ref "XJ2") (pin "62") (pinfunction "62_62") (pintype "unspecified"))
    )
    (net (code "142") (name "Net-(J2-Pad62)") (class "Default")
      (node (ref "J2") (pin "62") (pinfunction "62_62") (pintype "unspecified"))
      (node (ref "J3") (pin "62") (pinfunction "62_62") (pintype "unspecified"))
      (node (ref "XJ2") (pin "61") (pinfunction "61_61") (pintype "unspecified"))
    )
    (net (code "143") (name "Net-(J2-Pad63)") (class "Default")
      (node (ref "J2") (pin "63") (pinfunction "63_63") (pintype "unspecified"))
      (node (ref "J3") (pin "63") (pinfunction "63_63") (pintype "unspecified"))
      (node (ref "XJ2") (pin "64") (pinfunction "64_64") (pintype "unspecified"))
    )
    (net (code "144") (name "Net-(J2-Pad64)") (class "Default")
      (node (ref "J2") (pin "64") (pinfunction "64_64") (pintype "unspecified"))
      (node (ref "J3") (pin "64") (pinfunction "64_64") (pintype "unspecified"))
      (node (ref "XJ2") (pin "63") (pinfunction "63_63") (pintype "unspecified"))
    )
    (net (code "145") (name "Net-(J2-Pad65)") (class "Default")
      (node (ref "J2") (pin "65") (pinfunction "65_65") (pintype "unspecified"))
      (node (ref "J3") (pin "65") (pinfunction "65_65") (pintype "unspecified"))
      (node (ref "XJ2") (pin "66") (pinfunction "66_66") (pintype "unspecified"))
    )
    (net (code "146") (name "Net-(J2-Pad66)") (class "Default")
      (node (ref "J2") (pin "66") (pinfunction "66_66") (pintype "unspecified"))
      (node (ref "J3") (pin "66") (pinfunction "66_66") (pintype "unspecified"))
      (node (ref "XJ2") (pin "65") (pinfunction "65_65") (pintype "unspecified"))
    )
    (net (code "147") (name "Net-(J2-Pad67)") (class "Default")
      (node (ref "J2") (pin "67") (pinfunction "67_67") (pintype "unspecified"))
      (node (ref "J3") (pin "67") (pinfunction "67_67") (pintype "unspecified"))
      (node (ref "XJ2") (pin "68") (pinfunction "68_68") (pintype "unspecified"))
    )
    (net (code "148") (name "Net-(J2-Pad68)") (class "Default")
      (node (ref "J2") (pin "68") (pinfunction "68_68") (pintype "unspecified"))
      (node (ref "J3") (pin "68") (pinfunction "68_68") (pintype "unspecified"))
      (node (ref "XJ2") (pin "67") (pinfunction "67_67") (pintype "unspecified"))
    )
    (net (code "149") (name "Net-(J2-Pad69)") (class "Default")
      (node (ref "J2") (pin "69") (pinfunction "69_69") (pintype "unspecified"))
      (node (ref "J3") (pin "69") (pinfunction "69_69") (pintype "unspecified"))
      (node (ref "XJ2") (pin "70") (pinfunction "70_70") (pintype "unspecified"))
    )
    (net (code "150") (name "Net-(J2-Pad70)") (class "Default")
      (node (ref "J2") (pin "70") (pinfunction "70_70") (pintype "unspecified"))
      (node (ref "J3") (pin "70") (pinfunction "70_70") (pintype "unspecified"))
      (node (ref "XJ2") (pin "69") (pinfunction "69_69") (pintype "unspecified"))
    )
    (net (code "151") (name "Net-(J2-Pad71)") (class "Default")
      (node (ref "J2") (pin "71") (pinfunction "71_71") (pintype "unspecified"))
      (node (ref "J3") (pin "71") (pinfunction "71_71") (pintype "unspecified"))
      (node (ref "XJ2") (pin "72") (pinfunction "72_72") (pintype "unspecified"))
    )
    (net (code "152") (name "Net-(J2-Pad72)") (class "Default")
      (node (ref "J2") (pin "72") (pinfunction "72_72") (pintype "unspecified"))
      (node (ref "J3") (pin "72") (pinfunction "72_72") (pintype "unspecified"))
      (node (ref "XJ2") (pin "71") (pinfunction "71_71") (pintype "unspecified"))
    )
    (net (code "153") (name "Net-(J2-Pad73)") (class "Default")
      (node (ref "J2") (pin "73") (pinfunction "73_73") (pintype "unspecified"))
      (node (ref "J3") (pin "73") (pinfunction "73_73") (pintype "unspecified"))
      (node (ref "XJ2") (pin "74") (pinfunction "74_74") (pintype "unspecified"))
    )
    (net (code "154") (name "Net-(J2-Pad74)") (class "Default")
      (node (ref "J2") (pin "74") (pinfunction "74_74") (pintype "unspecified"))
      (node (ref "J3") (pin "74") (pinfunction "74_74") (pintype "unspecified"))
      (node (ref "XJ2") (pin "73") (pinfunction "73_73") (pintype "unspecified"))
    )
    (net (code "155") (name "Net-(J2-Pad75)") (class "Default")
      (node (ref "J2") (pin "75") (pinfunction "75_75") (pintype "unspecified"))
      (node (ref "J3") (pin "75") (pinfunction "75_75") (pintype "unspecified"))
      (node (ref "XJ2") (pin "76") (pinfunction "76_76") (pintype "unspecified"))
    )
    (net (code "156") (name "Net-(J2-Pad76)") (class "Default")
      (node (ref "J2") (pin "76") (pinfunction "76_76") (pintype "unspecified"))
      (node (ref "J3") (pin "76") (pinfunction "76_76") (pintype "unspecified"))
      (node (ref "XJ2") (pin "75") (pinfunction "75_75") (pintype "unspecified"))
    )
    (net (code "157") (name "Net-(J2-Pad77)") (class "Default")
      (node (ref "J2") (pin "77") (pinfunction "77_77") (pintype "unspecified"))
      (node (ref "J3") (pin "77") (pinfunction "77_77") (pintype "unspecified"))
      (node (ref "XJ2") (pin "78") (pinfunction "78_78") (pintype "unspecified"))
    )
    (net (code "158") (name "Net-(J2-Pad78)") (class "Default")
      (node (ref "J2") (pin "78") (pinfunction "78_78") (pintype "unspecified"))
      (node (ref "J3") (pin "78") (pinfunction "78_78") (pintype "unspecified"))
      (node (ref "XJ2") (pin "77") (pinfunction "77_77") (pintype "unspecified"))
    )
    (net (code "159") (name "Net-(J2-Pad79)") (class "Default")
      (node (ref "J2") (pin "79") (pinfunction "79_79") (pintype "unspecified"))
      (node (ref "J3") (pin "79") (pinfunction "79_79") (pintype "unspecified"))
      (node (ref "XJ2") (pin "80") (pinfunction "80_80") (pintype "unspecified"))
    )
    (net (code "160") (name "Net-(J2-Pad80)") (class "Default")
      (node (ref "J2") (pin "80") (pinfunction "80_80") (pintype "unspecified"))
      (node (ref "J3") (pin "80") (pinfunction "80_80") (pintype "unspecified"))
      (node (ref "XJ2") (pin "79") (pinfunction "79_79") (pintype "unspecified"))
    )
  )
)
